# Backplane.net
KiCad netlist of a schematic drawn in Altium Designer
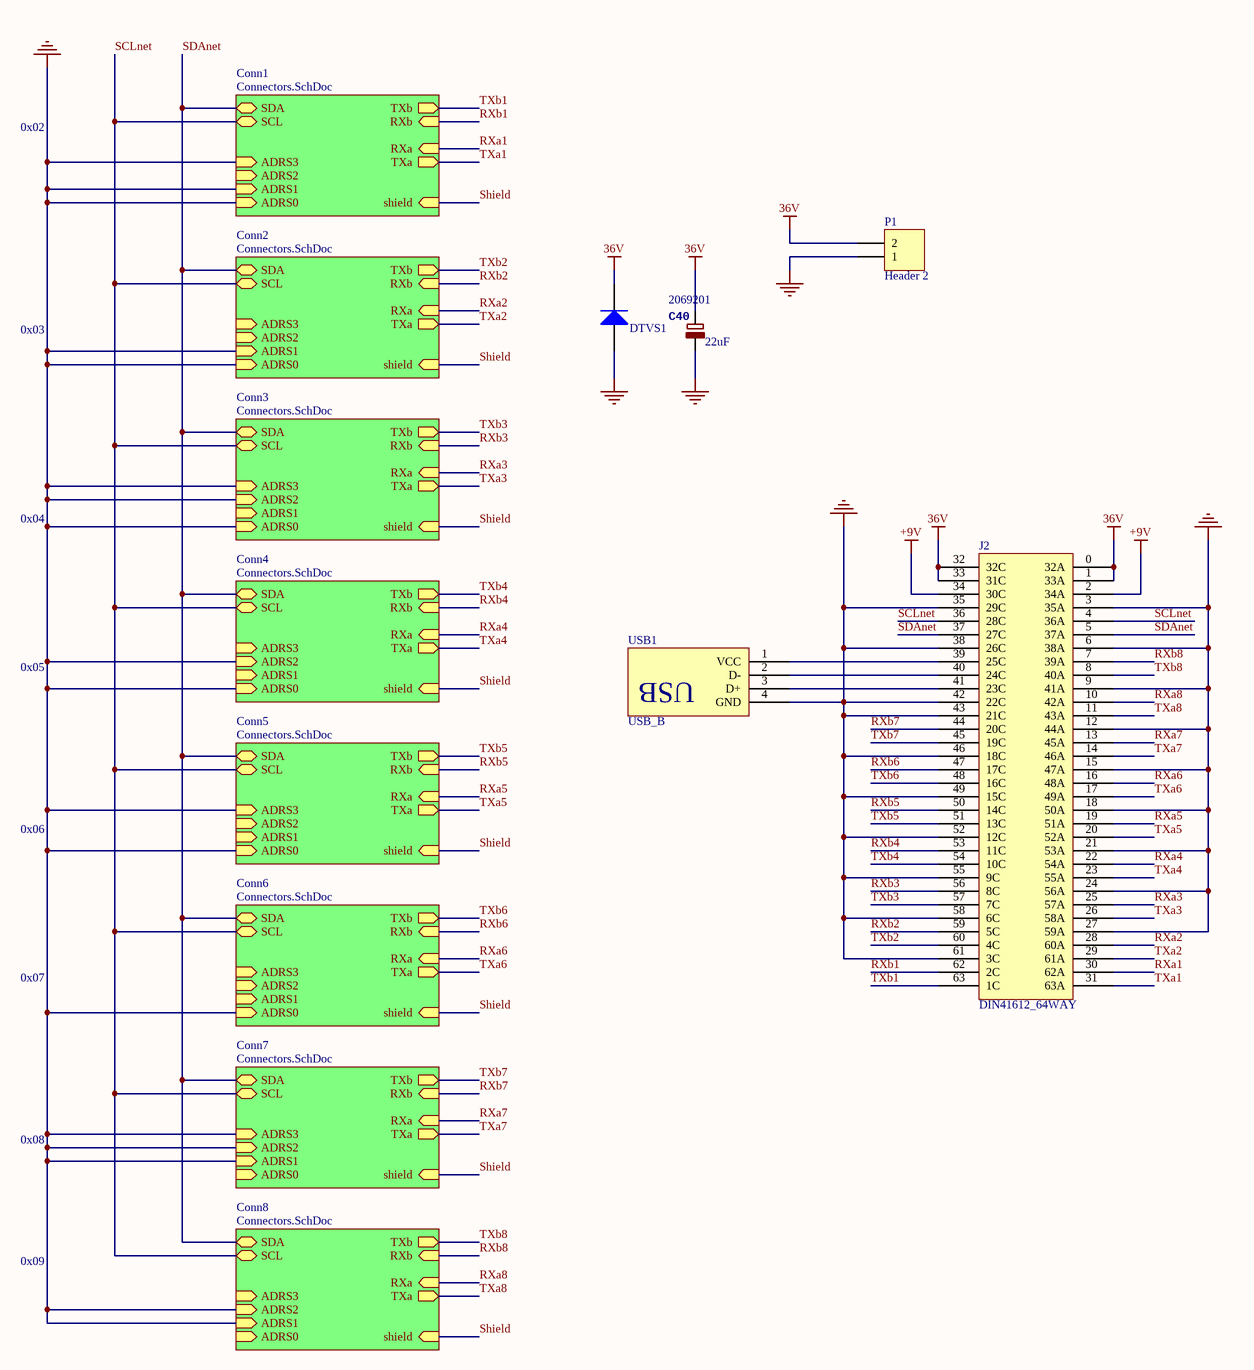
[diagram p0: Backplane.SchDoc]

(export (version "E")
  (design (tool "Eeschema 10.0.6"))
  (components
    (comp (ref "C40")
      (value "22uF")
      (footprint "PANASONIC_D")
      (fields (field (name "PARTNO") "EMZA500ADA220MF61G") (field (name "SUPPLIER PART NUMBER 1") "2069201"))
      (libsource (lib "G2_LV") (part "CPOL-EUD"))
    )
    (comp (ref "DTVS1")
      (value "SMBJ36A")
      (footprint "SMBJ")
      (description "TVS")
      (fields (field (name "PUBLISHER") "Altium Limited"))
      (libsource (lib "G2_LV") (part "SMBJ"))
    )
    (comp (ref "J2")
      (value "DIN41612_64WAY")
      (footprint "09 03 164 6919")
      (fields (field (name "PARTNO") "9-1393640-3"))
      (libsource (lib "BACKPLANElib") (part "DIN41612_64WAY"))
    )
    (comp (ref "P1")
      (value "Header 2")
      (footprint "8PCV")
      (description "Header, 2-Pin")
      (fields (field (name "PARTNO") "8PCV-02-006") (field (name "PUBLISHER") "Altium Limited"))
      (libsource (lib "Miscellaneous Connectors") (part "Header 2"))
    )
    (comp (ref "USB1")
      (value "USB_B")
      (footprint "USB_B_VERTICAL")
      (libsource (lib "BACKPLANElib") (part "USB_B"))
    )
  )
  (nets
    (net (code "1") (name "+9V") (class "Default")
      (node (ref "J2") (pin "2") (pinfunction "34A_2") (pintype "passive"))
      (node (ref "J2") (pin "34") (pinfunction "30C_34") (pintype "passive"))
    )
    (net (code "16") (name "/RXa1") (class "Default")
      (node (ref "J2") (pin "30") (pinfunction "62A_30") (pintype "passive"))
    )
    (net (code "17") (name "/RXa2") (class "Default")
      (node (ref "J2") (pin "28") (pinfunction "60A_28") (pintype "passive"))
    )
    (net (code "18") (name "/RXa3") (class "Default")
      (node (ref "J2") (pin "25") (pinfunction "57A_25") (pintype "passive"))
    )
    (net (code "19") (name "/RXa4") (class "Default")
      (node (ref "J2") (pin "22") (pinfunction "54A_22") (pintype "passive"))
    )
    (net (code "20") (name "/RXa5") (class "Default")
      (node (ref "J2") (pin "19") (pinfunction "51A_19") (pintype "passive"))
    )
    (net (code "21") (name "/RXa6") (class "Default")
      (node (ref "J2") (pin "16") (pinfunction "48A_16") (pintype "passive"))
    )
    (net (code "22") (name "/RXa7") (class "Default")
      (node (ref "J2") (pin "13") (pinfunction "45A_13") (pintype "passive"))
    )
    (net (code "23") (name "/RXa8") (class "Default")
      (node (ref "J2") (pin "10") (pinfunction "42A_10") (pintype "passive"))
    )
    (net (code "24") (name "/RXb1") (class "Default")
      (node (ref "J2") (pin "62") (pinfunction "2C_62") (pintype "passive"))
    )
    (net (code "25") (name "/RXb2") (class "Default")
      (node (ref "J2") (pin "59") (pinfunction "5C_59") (pintype "passive"))
    )
    (net (code "26") (name "/RXb3") (class "Default")
      (node (ref "J2") (pin "56") (pinfunction "8C_56") (pintype "passive"))
    )
    (net (code "27") (name "/RXb4") (class "Default")
      (node (ref "J2") (pin "53") (pinfunction "11C_53") (pintype "passive"))
    )
    (net (code "28") (name "/RXb5") (class "Default")
      (node (ref "J2") (pin "50") (pinfunction "14C_50") (pintype "passive"))
    )
    (net (code "29") (name "/RXb6") (class "Default")
      (node (ref "J2") (pin "47") (pinfunction "17C_47") (pintype "passive"))
    )
    (net (code "30") (name "/RXb7") (class "Default")
      (node (ref "J2") (pin "44") (pinfunction "20C_44") (pintype "passive"))
    )
    (net (code "31") (name "/RXb8") (class "Default")
      (node (ref "J2") (pin "7") (pinfunction "39A_7") (pintype "passive"))
    )
    (net (code "32") (name "/SCLnet") (class "Default")
      (node (ref "J2") (pin "36") (pinfunction "28C_36") (pintype "passive"))
      (node (ref "J2") (pin "4") (pinfunction "36A_4") (pintype "passive"))
    )
    (net (code "33") (name "/SDAnet") (class "Default")
      (node (ref "J2") (pin "37") (pinfunction "27C_37") (pintype "passive"))
      (node (ref "J2") (pin "5") (pinfunction "37A_5") (pintype "passive"))
    )
    (net (code "35") (name "/TXa1") (class "Default")
      (node (ref "J2") (pin "31") (pinfunction "63A_31") (pintype "passive"))
    )
    (net (code "36") (name "/TXa2") (class "Default")
      (node (ref "J2") (pin "29") (pinfunction "61A_29") (pintype "passive"))
    )
    (net (code "37") (name "/TXa3") (class "Default")
      (node (ref "J2") (pin "26") (pinfunction "58A_26") (pintype "passive"))
    )
    (net (code "38") (name "/TXa4") (class "Default")
      (node (ref "J2") (pin "23") (pinfunction "55A_23") (pintype "passive"))
    )
    (net (code "39") (name "/TXa5") (class "Default")
      (node (ref "J2") (pin "20") (pinfunction "52A_20") (pintype "passive"))
    )
    (net (code "40") (name "/TXa6") (class "Default")
      (node (ref "J2") (pin "17") (pinfunction "49A_17") (pintype "passive"))
    )
    (net (code "41") (name "/TXa7") (class "Default")
      (node (ref "J2") (pin "14") (pinfunction "46A_14") (pintype "passive"))
    )
    (net (code "42") (name "/TXa8") (class "Default")
      (node (ref "J2") (pin "11") (pinfunction "43A_11") (pintype "passive"))
    )
    (net (code "43") (name "/TXb1") (class "Default")
      (node (ref "J2") (pin "63") (pinfunction "1C_63") (pintype "passive"))
    )
    (net (code "44") (name "/TXb2") (class "Default")
      (node (ref "J2") (pin "60") (pinfunction "4C_60") (pintype "passive"))
    )
    (net (code "45") (name "/TXb3") (class "Default")
      (node (ref "J2") (pin "57") (pinfunction "7C_57") (pintype "passive"))
    )
    (net (code "46") (name "/TXb4") (class "Default")
      (node (ref "J2") (pin "54") (pinfunction "10C_54") (pintype "passive"))
    )
    (net (code "47") (name "/TXb5") (class "Default")
      (node (ref "J2") (pin "51") (pinfunction "13C_51") (pintype "passive"))
    )
    (net (code "48") (name "/TXb6") (class "Default")
      (node (ref "J2") (pin "48") (pinfunction "16C_48") (pintype "passive"))
    )
    (net (code "49") (name "/TXb7") (class "Default")
      (node (ref "J2") (pin "45") (pinfunction "19C_45") (pintype "passive"))
    )
    (net (code "50") (name "/TXb8") (class "Default")
      (node (ref "J2") (pin "8") (pinfunction "40A_8") (pintype "passive"))
    )
    (net (code "51") (name "36V") (class "Default")
      (node (ref "C40") (pin "1") (pinfunction "1_1") (pintype "passive"))
      (node (ref "DTVS1") (pin "1") (pinfunction "K_1") (pintype "passive"))
      (node (ref "J2") (pin "0") (pinfunction "32A_0") (pintype "passive"))
      (node (ref "J2") (pin "1") (pinfunction "33A_1") (pintype "passive"))
      (node (ref "J2") (pin "32") (pinfunction "32C_32") (pintype "passive"))
      (node (ref "J2") (pin "33") (pinfunction "31C_33") (pintype "passive"))
      (node (ref "P1") (pin "2") (pinfunction "2_2") (pintype "passive"))
    )
    (net (code "52") (name "GND") (class "Default")
      (node (ref "C40") (pin "2") (pinfunction "2_2") (pintype "passive"))
      (node (ref "DTVS1") (pin "2") (pinfunction "A_2") (pintype "passive"))
      (node (ref "J2") (pin "12") (pinfunction "44A_12") (pintype "passive"))
      (node (ref "J2") (pin "15") (pinfunction "47A_15") (pintype "passive"))
      (node (ref "J2") (pin "18") (pinfunction "50A_18") (pintype "passive"))
      (node (ref "J2") (pin "21") (pinfunction "53A_21") (pintype "passive"))
      (node (ref "J2") (pin "24") (pinfunction "56A_24") (pintype "passive"))
      (node (ref "J2") (pin "27") (pinfunction "59A_27") (pintype "passive"))
      (node (ref "J2") (pin "3") (pinfunction "35A_3") (pintype "passive"))
      (node (ref "J2") (pin "35") (pinfunction "29C_35") (pintype "passive"))
      (node (ref "J2") (pin "38") (pinfunction "26C_38") (pintype "passive"))
      (node (ref "J2") (pin "42") (pinfunction "22C_42") (pintype "passive"))
      (node (ref "J2") (pin "43") (pinfunction "21C_43") (pintype "passive"))
      (node (ref "J2") (pin "46") (pinfunction "18C_46") (pintype "passive"))
      (node (ref "J2") (pin "49") (pinfunction "15C_49") (pintype "passive"))
      (node (ref "J2") (pin "52") (pinfunction "12C_52") (pintype "passive"))
      (node (ref "J2") (pin "55") (pinfunction "9C_55") (pintype "passive"))
      (node (ref "J2") (pin "58") (pinfunction "6C_58") (pintype "passive"))
      (node (ref "J2") (pin "6") (pinfunction "38A_6") (pintype "passive"))
      (node (ref "J2") (pin "61") (pinfunction "3C_61") (pintype "passive"))
      (node (ref "J2") (pin "9") (pinfunction "41A_9") (pintype "passive"))
      (node (ref "P1") (pin "1") (pinfunction "1_1") (pintype "passive"))
      (node (ref "USB1") (pin "4") (pinfunction "GND_4") (pintype "passive"))
    )
    (net (code "53") (name "Net-(J2-23C)") (class "Default")
      (node (ref "J2") (pin "41") (pinfunction "23C_41") (pintype "passive"))
      (node (ref "USB1") (pin "3") (pinfunction "D+_3") (pintype "passive"))
    )
    (net (code "54") (name "Net-(J2-24C)") (class "Default")
      (node (ref "J2") (pin "40") (pinfunction "24C_40") (pintype "passive"))
      (node (ref "USB1") (pin "2") (pinfunction "D-_2") (pintype "passive"))
    )
    (net (code "55") (name "Net-(J2-25C)") (class "Default")
      (node (ref "J2") (pin "39") (pinfunction "25C_39") (pintype "passive"))
      (node (ref "USB1") (pin "1") (pinfunction "VCC_1") (pintype "passive"))
    )
  )
)
